# DSOBoard.net
KiCad netlist of a schematic drawn in Altium Designer
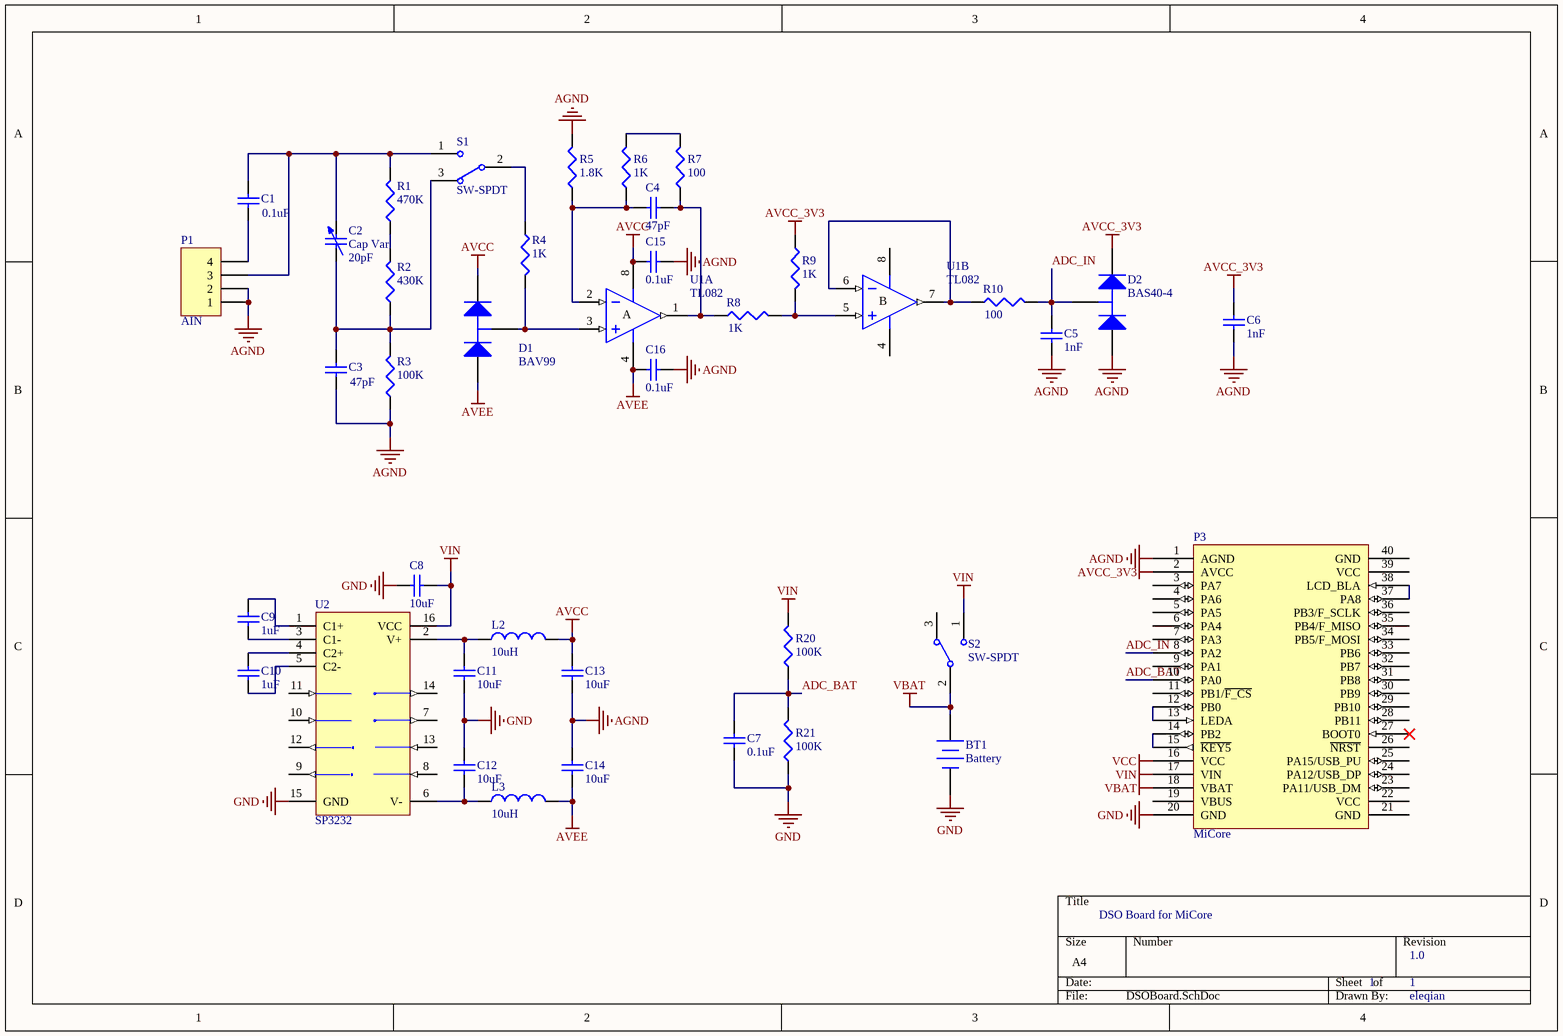
[diagram p0: DSOBoard.SchDoc]

(export (version "E")
  (design (tool "Eeschema 10.0.6"))
  (components
    (comp (ref "BT1")
      (value "Battery")
      (footprint "BAT-2")
      (description "Multicell Battery")
      (fields (field (name "PUBLISHER") "Altium Limited"))
      (libsource (lib "Miscellaneous Devices") (part "Battery"))
    )
    (comp (ref "C1")
      (value "0.1uF")
      (footprint "0805C")
      (description "Capacitor")
      (fields (field (name "Comment") "Cap") (field (name "PUBLISHER") "Altium Limited"))
      (libsource (lib "Miscellaneous Devices") (part "Cap"))
    )
    (comp (ref "C2")
      (value "Cap Var")
      (footprint "C1210_N")
      (description "Variable or Adjustable Capacitor")
      (fields (field (name "ALTIUM_VALUE") "20pF") (field (name "PUBLISHER") "Altium Limited"))
      (libsource (lib "Miscellaneous Devices") (part "Cap Var"))
    )
    (comp (ref "C3")
      (value "47pF")
      (footprint "0603C")
      (description "Capacitor")
      (fields (field (name "Comment") "Cap"))
      (libsource (lib "Miscellaneous Devices") (part "Cap"))
    )
    (comp (ref "C4")
      (value "47pF")
      (footprint "0603C")
      (description "Capacitor")
      (fields (field (name "Comment") "Cap"))
      (libsource (lib "Miscellaneous Devices") (part "Cap"))
    )
    (comp (ref "C5")
      (value "1nF")
      (footprint "0603C")
      (description "Capacitor")
      (fields (field (name "Comment") "Cap"))
      (libsource (lib "Miscellaneous Devices") (part "Cap"))
    )
    (comp (ref "C6")
      (value "1nF")
      (footprint "0603C")
      (description "Capacitor")
      (fields (field (name "Comment") "Cap"))
      (libsource (lib "Miscellaneous Devices") (part "Cap"))
    )
    (comp (ref "C7")
      (value "0.1uF")
      (footprint "0603C")
      (description "Capacitor")
      (fields (field (name "Comment") "Cap"))
      (libsource (lib "Miscellaneous Devices") (part "Cap"))
    )
    (comp (ref "C8")
      (value "10uF")
      (footprint "0603C")
      (description "Capacitor")
      (fields (field (name "Comment") "Cap") (field (name "PUBLISHER") "Altium Limited"))
      (libsource (lib "Miscellaneous Devices") (part "Cap"))
    )
    (comp (ref "C9")
      (value "1uF")
      (footprint "0603C")
      (description "Capacitor")
      (fields (field (name "Comment") "Cap") (field (name "PUBLISHER") "Altium Limited"))
      (libsource (lib "Miscellaneous Devices") (part "Cap"))
    )
    (comp (ref "C10")
      (value "1uF")
      (footprint "0603C")
      (description "Capacitor")
      (fields (field (name "Comment") "Cap") (field (name "PUBLISHER") "Altium Limited"))
      (libsource (lib "Miscellaneous Devices") (part "Cap"))
    )
    (comp (ref "C11")
      (value "10uF")
      (footprint "0603C")
      (description "Capacitor")
      (fields (field (name "Comment") "Cap") (field (name "PUBLISHER") "Altium Limited"))
      (libsource (lib "Miscellaneous Devices") (part "Cap"))
    )
    (comp (ref "C12")
      (value "10uF")
      (footprint "0603C")
      (description "Capacitor")
      (fields (field (name "Comment") "Cap") (field (name "PUBLISHER") "Altium Limited"))
      (libsource (lib "Miscellaneous Devices") (part "Cap"))
    )
    (comp (ref "C13")
      (value "10uF")
      (footprint "0603C")
      (description "Capacitor")
      (fields (field (name "Comment") "Cap"))
      (libsource (lib "Miscellaneous Devices") (part "Cap"))
    )
    (comp (ref "C14")
      (value "10uF")
      (footprint "0603C")
      (description "Capacitor")
      (fields (field (name "Comment") "Cap"))
      (libsource (lib "Miscellaneous Devices") (part "Cap"))
    )
    (comp (ref "C15")
      (value "0.1uF")
      (footprint "0603C")
      (description "Capacitor")
      (fields (field (name "Comment") "Cap"))
      (libsource (lib "Miscellaneous Devices") (part "Cap"))
    )
    (comp (ref "C16")
      (value "0.1uF")
      (footprint "0603C")
      (description "Capacitor")
      (fields (field (name "Comment") "Cap"))
      (libsource (lib "Miscellaneous Devices") (part "Cap"))
    )
    (comp (ref "D1")
      (value "BAV99")
      (footprint "SOT-23")
      (description "SOT23 Silicon Planar High-Speed Switching Series Diode Pair")
      (fields (field (name "PUBLISHER") "Altium Limited"))
      (libsource (lib "Zetex Discrete Diode") (part "BAV99"))
    )
    (comp (ref "D2")
      (value "BAS40-4")
      (footprint "SOT-23")
      (description "SOT23 Silicon Planar High-Speed Switching Series Diode Pair")
      (fields (field (name "PUBLISHER") "Altium Limited"))
      (libsource (lib "Zetex Discrete Diode") (part "BAV99"))
    )
    (comp (ref "L2")
      (value "10uH")
      (footprint "0805L")
      (description "Inductor")
      (fields (field (name "PUBLISHER") "Altium Limited"))
      (libsource (lib "Miscellaneous Devices") (part "Inductor"))
    )
    (comp (ref "L3")
      (value "10uH")
      (footprint "0805L")
      (description "Inductor")
      (fields (field (name "PUBLISHER") "Altium Limited"))
      (libsource (lib "Miscellaneous Devices") (part "Inductor"))
    )
    (comp (ref "P1")
      (value "AIN")
      (footprint "HDR1X4")
      (description "Header, 4-Pin")
      (fields (field (name "PUBLISHER") "Altium Limited"))
      (libsource (lib "Miscellaneous Connectors") (part "Header 4"))
    )
    (comp (ref "P3") (value "MiCore") (description "MiCore核心板") (libsource (lib "MiCore") (part "MiCore")))
    (comp (ref "R1")
      (value "470K")
      (footprint "0603R")
      (description "Resistor")
      (fields (field (name "Comment") "Res3") (field (name "PUBLISHER") "Altium Limited"))
      (libsource (lib "Miscellaneous Devices") (part "Res3"))
    )
    (comp (ref "R2")
      (value "430K")
      (footprint "0603R")
      (description "Resistor")
      (fields (field (name "Comment") "Res3") (field (name "PUBLISHER") "Altium Limited"))
      (libsource (lib "Miscellaneous Devices") (part "Res3"))
    )
    (comp (ref "R3")
      (value "100K")
      (footprint "0603R")
      (description "Resistor")
      (fields (field (name "Comment") "Res3") (field (name "PUBLISHER") "Altium Limited"))
      (libsource (lib "Miscellaneous Devices") (part "Res3"))
    )
    (comp (ref "R4")
      (value "1K")
      (footprint "0603R")
      (description "Resistor")
      (fields (field (name "Comment") "Res3") (field (name "PUBLISHER") "Altium Limited"))
      (libsource (lib "Miscellaneous Devices") (part "Res3"))
    )
    (comp (ref "R5")
      (value "1.8K")
      (footprint "0603R")
      (description "Resistor")
      (fields (field (name "Comment") "Res3") (field (name "PUBLISHER") "Altium Limited"))
      (libsource (lib "Miscellaneous Devices") (part "Res3"))
    )
    (comp (ref "R6")
      (value "1K")
      (footprint "0603R")
      (description "Resistor")
      (fields (field (name "Comment") "Res3") (field (name "PUBLISHER") "Altium Limited"))
      (libsource (lib "Miscellaneous Devices") (part "Res3"))
    )
    (comp (ref "R7")
      (value "100")
      (footprint "0603R")
      (description "Resistor")
      (fields (field (name "Comment") "Res3") (field (name "PUBLISHER") "Altium Limited"))
      (libsource (lib "Miscellaneous Devices") (part "Res3"))
    )
    (comp (ref "R8")
      (value "1K")
      (footprint "0603R")
      (description "Resistor")
      (fields (field (name "Comment") "Res3") (field (name "PUBLISHER") "Altium Limited"))
      (libsource (lib "Miscellaneous Devices") (part "Res3"))
    )
    (comp (ref "R9")
      (value "1K")
      (footprint "0603R")
      (description "Resistor")
      (fields (field (name "Comment") "Res3") (field (name "PUBLISHER") "Altium Limited"))
      (libsource (lib "Miscellaneous Devices") (part "Res3"))
    )
    (comp (ref "R10")
      (value "100")
      (footprint "0603R")
      (description "Resistor")
      (fields (field (name "Comment") "Res3") (field (name "PUBLISHER") "Altium Limited"))
      (libsource (lib "Miscellaneous Devices") (part "Res3"))
    )
    (comp (ref "R20")
      (value "100K")
      (footprint "0603R")
      (description "Resistor")
      (fields (field (name "Comment") "Res3") (field (name "PUBLISHER") "Altium Limited"))
      (libsource (lib "Miscellaneous Devices") (part "Res3"))
    )
    (comp (ref "R21")
      (value "100K")
      (footprint "0603R")
      (description "Resistor")
      (fields (field (name "Comment") "Res3") (field (name "PUBLISHER") "Altium Limited"))
      (libsource (lib "Miscellaneous Devices") (part "Res3"))
    )
    (comp (ref "S1")
      (value "SW-SPDT")
      (footprint "SPDT_3S")
      (description "SPDT Subminiature Toggle Switch, Right Angle Mounting, Vertical Actuation")
      (fields (field (name "PUBLISHER") "Altium Limited"))
      (libsource (lib "Miscellaneous Devices") (part "SW-SPDT"))
    )
    (comp (ref "S2")
      (value "SW-SPDT")
      (footprint "SPDT_3S")
      (description "SPDT Subminiature Toggle Switch, Right Angle Mounting, Vertical Actuation")
      (fields (field (name "PUBLISHER") "Altium Limited"))
      (libsource (lib "Miscellaneous Devices") (part "SW-SPDT"))
    )
    (comp (ref "U1")
      (value "TL082")
      (footprint "SO-8_N")
      (description "Dual, 16MHz, Rail-to-Rail FET-Input Amplifier")
      (fields (field (name "PUBLISHER") "Altium Limited"))
      (libsource (lib "AD Operational Amplifier") (part "AD823AR"))
    )
    (comp (ref "U2")
      (value "SP3232")
      (footprint "NSO16_N")
      (description "3.0V TO 5.5V, Low-Power, up to 1Mbps, True RS-232 Transceiver Using Four 0.1µF External Capacitor")
      (fields (field (name "PUBLISHER") "Altium Limited"))
      (libsource (lib "Maxim Communication Transceiver") (part "MAX3232CSE"))
    )
  )
  (nets
    (net (code "1") (name "/ADC_BAT") (class "Default")
      (node (ref "C7") (pin "2") (pinfunction "2_2") (pintype "passive"))
      (node (ref "P3") (pin "10") (pinfunction "PA0_10") (pintype "bidirectional"))
      (node (ref "R20") (pin "1") (pinfunction "1_1") (pintype "passive"))
      (node (ref "R21") (pin "2") (pinfunction "2_2") (pintype "passive"))
    )
    (net (code "2") (name "/ADC_IN") (class "Default")
      (node (ref "C5") (pin "2") (pinfunction "2_2") (pintype "passive"))
      (node (ref "D2") (pin "1") (pinfunction "C_1") (pintype "passive"))
      (node (ref "P3") (pin "8") (pinfunction "PA2_8") (pintype "bidirectional"))
      (node (ref "R10") (pin "2") (pinfunction "2_2") (pintype "passive"))
    )
    (net (code "3") (name "AGND") (class "Default")
      (node (ref "C13") (pin "2") (pinfunction "2_2") (pintype "passive"))
      (node (ref "C14") (pin "1") (pinfunction "1_1") (pintype "passive"))
      (node (ref "C15") (pin "1") (pinfunction "1_1") (pintype "passive"))
      (node (ref "C16") (pin "1") (pinfunction "1_1") (pintype "passive"))
      (node (ref "C3") (pin "1") (pinfunction "1_1") (pintype "passive"))
      (node (ref "C5") (pin "1") (pinfunction "1_1") (pintype "passive"))
      (node (ref "C6") (pin "1") (pinfunction "1_1") (pintype "passive"))
      (node (ref "D2") (pin "3") (pinfunction "A_3") (pintype "passive"))
      (node (ref "P1") (pin "1") (pinfunction "1_1") (pintype "passive"))
      (node (ref "P1") (pin "2") (pinfunction "2_2") (pintype "passive"))
      (node (ref "P3") (pin "1") (pinfunction "AGND_1") (pintype "power_in"))
      (node (ref "R3") (pin "1") (pinfunction "1_1") (pintype "passive"))
      (node (ref "R5") (pin "2") (pinfunction "2_2") (pintype "passive"))
    )
    (net (code "4") (name "AVCC") (class "Default")
      (node (ref "C13") (pin "1") (pinfunction "1_1") (pintype "passive"))
      (node (ref "C15") (pin "2") (pinfunction "2_2") (pintype "passive"))
      (node (ref "D1") (pin "2") (pinfunction "K_2") (pintype "passive"))
      (node (ref "L2") (pin "2") (pinfunction "2_2") (pintype "passive"))
      (node (ref "U1") (pin "8") (pinfunction "V+_8") (pintype "power_in"))
    )
    (net (code "5") (name "AVCC_3V3") (class "Default")
      (node (ref "C6") (pin "2") (pinfunction "2_2") (pintype "passive"))
      (node (ref "D2") (pin "2") (pinfunction "K_2") (pintype "passive"))
      (node (ref "P3") (pin "2") (pinfunction "AVCC_2") (pintype "power_in"))
      (node (ref "R9") (pin "1") (pinfunction "1_1") (pintype "passive"))
    )
    (net (code "6") (name "AVEE") (class "Default")
      (node (ref "C14") (pin "2") (pinfunction "2_2") (pintype "passive"))
      (node (ref "C16") (pin "2") (pinfunction "2_2") (pintype "passive"))
      (node (ref "D1") (pin "3") (pinfunction "A_3") (pintype "passive"))
      (node (ref "L3") (pin "2") (pinfunction "2_2") (pintype "passive"))
      (node (ref "U1") (pin "4") (pinfunction "V-_4") (pintype "power_in"))
    )
    (net (code "7") (name "GND") (class "Default")
      (node (ref "BT1") (pin "2") (pinfunction "-_2") (pintype "passive"))
      (node (ref "C11") (pin "2") (pinfunction "2_2") (pintype "passive"))
      (node (ref "C12") (pin "2") (pinfunction "2_2") (pintype "passive"))
      (node (ref "C7") (pin "1") (pinfunction "1_1") (pintype "passive"))
      (node (ref "C8") (pin "2") (pinfunction "2_2") (pintype "passive"))
      (node (ref "P3") (pin "20") (pinfunction "GND_20") (pintype "power_in"))
      (node (ref "R21") (pin "1") (pinfunction "1_1") (pintype "passive"))
      (node (ref "U2") (pin "15") (pinfunction "GND_15") (pintype "power_in"))
    )
    (net (code "8") (name "Net-(C1-Pad1)") (class "Default")
      (node (ref "C1") (pin "1") (pinfunction "1_1") (pintype "passive"))
      (node (ref "C2") (pin "2") (pinfunction "2_2") (pintype "passive"))
      (node (ref "P1") (pin "3") (pinfunction "3_3") (pintype "passive"))
      (node (ref "R1") (pin "2") (pinfunction "2_2") (pintype "passive"))
      (node (ref "S1") (pin "1") (pinfunction "1_1") (pintype "passive"))
    )
    (net (code "9") (name "Net-(C1-Pad2)") (class "Default")
      (node (ref "C1") (pin "2") (pinfunction "2_2") (pintype "passive"))
      (node (ref "P1") (pin "4") (pinfunction "4_4") (pintype "passive"))
    )
    (net (code "10") (name "Net-(C2-Pad1)") (class "Default")
      (node (ref "C2") (pin "1") (pinfunction "1_1") (pintype "passive"))
      (node (ref "C3") (pin "2") (pinfunction "2_2") (pintype "passive"))
      (node (ref "R2") (pin "1") (pinfunction "1_1") (pintype "passive"))
      (node (ref "R3") (pin "2") (pinfunction "2_2") (pintype "passive"))
      (node (ref "S1") (pin "3") (pinfunction "3_3") (pintype "passive"))
    )
    (net (code "11") (name "Net-(D1-C)") (class "Default")
      (node (ref "D1") (pin "1") (pinfunction "C_1") (pintype "passive"))
      (node (ref "R4") (pin "2") (pinfunction "2_2") (pintype "passive"))
      (node (ref "U1") (pin "3") (pinfunction "IN+_3") (pintype "input"))
    )
    (net (code "12") (name "Net-(P3-LCD_BLA)") (class "Default")
      (node (ref "P3") (pin "37") (pinfunction "PA8_37") (pintype "bidirectional"))
      (node (ref "P3") (pin "38") (pinfunction "LCD_BLA_38") (pintype "input"))
    )
    (net (code "13") (name "Net-(P3-LEDA)") (class "Default")
      (node (ref "P3") (pin "12") (pinfunction "PB0_12") (pintype "bidirectional"))
      (node (ref "P3") (pin "13") (pinfunction "LEDA_13") (pintype "input"))
    )
    (net (code "14") (name "Net-(P3-PB2)") (class "Default")
      (node (ref "P3") (pin "14") (pinfunction "PB2_14") (pintype "bidirectional"))
      (node (ref "P3") (pin "15") (pinfunction "~{KEY5}_15") (pintype "output"))
    )
    (net (code "15") (name "Net-(R1-Pad1)") (class "Default")
      (node (ref "R1") (pin "1") (pinfunction "1_1") (pintype "passive"))
      (node (ref "R2") (pin "2") (pinfunction "2_2") (pintype "passive"))
    )
    (net (code "16") (name "Net-(R4-Pad1)") (class "Default")
      (node (ref "R4") (pin "1") (pinfunction "1_1") (pintype "passive"))
      (node (ref "S1") (pin "2") (pinfunction "2_2") (pintype "passive"))
    )
    (net (code "17") (name "Net-(R6-Pad2)") (class "Default")
      (node (ref "R6") (pin "2") (pinfunction "2_2") (pintype "passive"))
      (node (ref "R7") (pin "2") (pinfunction "2_2") (pintype "passive"))
    )
    (net (code "18") (name "Net-(U1A-IN-)") (class "Default")
      (node (ref "C4") (pin "2") (pinfunction "2_2") (pintype "passive"))
      (node (ref "R5") (pin "1") (pinfunction "1_1") (pintype "passive"))
      (node (ref "R6") (pin "1") (pinfunction "1_1") (pintype "passive"))
      (node (ref "U1") (pin "2") (pinfunction "IN-_2") (pintype "input"))
    )
    (net (code "19") (name "Net-(U1A-OUT)") (class "Default")
      (node (ref "C4") (pin "1") (pinfunction "1_1") (pintype "passive"))
      (node (ref "R7") (pin "1") (pinfunction "1_1") (pintype "passive"))
      (node (ref "R8") (pin "1") (pinfunction "1_1") (pintype "passive"))
      (node (ref "U1") (pin "1") (pinfunction "OUT_1") (pintype "output"))
    )
    (net (code "20") (name "Net-(U1B-IN+)") (class "Default")
      (node (ref "R8") (pin "2") (pinfunction "2_2") (pintype "passive"))
      (node (ref "R9") (pin "2") (pinfunction "2_2") (pintype "passive"))
      (node (ref "U1") (pin "5") (pinfunction "IN+_5") (pintype "input"))
    )
    (net (code "21") (name "Net-(U1B-IN-)") (class "Default")
      (node (ref "R10") (pin "1") (pinfunction "1_1") (pintype "passive"))
      (node (ref "U1") (pin "6") (pinfunction "IN-_6") (pintype "input"))
      (node (ref "U1") (pin "7") (pinfunction "OUT_7") (pintype "output"))
    )
    (net (code "22") (name "Net-(U2-C1+)") (class "Default")
      (node (ref "C9") (pin "1") (pinfunction "1_1") (pintype "passive"))
      (node (ref "U2") (pin "1") (pinfunction "C1+_1") (pintype "passive"))
    )
    (net (code "23") (name "Net-(U2-C1-)") (class "Default")
      (node (ref "C9") (pin "2") (pinfunction "2_2") (pintype "passive"))
      (node (ref "U2") (pin "3") (pinfunction "C1-_3") (pintype "passive"))
    )
    (net (code "24") (name "Net-(U2-C2+)") (class "Default")
      (node (ref "C10") (pin "1") (pinfunction "1_1") (pintype "passive"))
      (node (ref "U2") (pin "4") (pinfunction "C2+_4") (pintype "passive"))
    )
    (net (code "25") (name "Net-(U2-C2-)") (class "Default")
      (node (ref "C10") (pin "2") (pinfunction "2_2") (pintype "passive"))
      (node (ref "U2") (pin "5") (pinfunction "C2-_5") (pintype "passive"))
    )
    (net (code "26") (name "Net-(U2-V+)") (class "Default")
      (node (ref "C11") (pin "1") (pinfunction "1_1") (pintype "passive"))
      (node (ref "L2") (pin "1") (pinfunction "1_1") (pintype "passive"))
      (node (ref "U2") (pin "2") (pinfunction "V+_2") (pintype "power_in"))
    )
    (net (code "27") (name "Net-(U2-V-)") (class "Default")
      (node (ref "C12") (pin "1") (pinfunction "1_1") (pintype "passive"))
      (node (ref "L3") (pin "1") (pinfunction "1_1") (pintype "passive"))
      (node (ref "U2") (pin "6") (pinfunction "V-_6") (pintype "power_in"))
    )
    (net (code "28") (name "VBAT") (class "Default")
      (node (ref "BT1") (pin "1") (pinfunction "+_1") (pintype "passive"))
      (node (ref "P3") (pin "18") (pinfunction "VBAT_18") (pintype "power_in"))
      (node (ref "S2") (pin "2") (pinfunction "2_2") (pintype "passive"))
    )
    (net (code "29") (name "VCC") (class "Default")
      (node (ref "P3") (pin "16") (pinfunction "VCC_16") (pintype "power_in"))
    )
    (net (code "30") (name "VIN") (class "Default")
      (node (ref "C8") (pin "1") (pinfunction "1_1") (pintype "passive"))
      (node (ref "P3") (pin "17") (pinfunction "VIN_17") (pintype "power_in"))
      (node (ref "R20") (pin "2") (pinfunction "2_2") (pintype "passive"))
      (node (ref "S2") (pin "1") (pinfunction "1_1") (pintype "passive"))
      (node (ref "U2") (pin "16") (pinfunction "VCC_16") (pintype "power_in"))
    )
    (net (code "31") (name "unconnected-(P3-BOOT0-Pad27)") (class "Default")
      (node (ref "P3") (pin "27") (pinfunction "BOOT0_27") (pintype "input+no_connect"))
    )
    (net (code "32") (name "unconnected-(P3-GND-Pad21)") (class "Default")
      (node (ref "P3") (pin "21") (pinfunction "GND_21") (pintype "power_in"))
    )
    (net (code "33") (name "unconnected-(P3-GND-Pad40)") (class "Default")
      (node (ref "P3") (pin "40") (pinfunction "GND_40") (pintype "power_in"))
    )
    (net (code "34") (name "unconnected-(P3-PA1-Pad9)") (class "Default")
      (node (ref "P3") (pin "9") (pinfunction "PA1_9") (pintype "bidirectional"))
    )
    (net (code "35") (name "unconnected-(P3-PA3-Pad7)") (class "Default")
      (node (ref "P3") (pin "7") (pinfunction "PA3_7") (pintype "bidirectional"))
    )
    (net (code "36") (name "unconnected-(P3-PA4-Pad6)") (class "Default")
      (node (ref "P3") (pin "6") (pinfunction "PA4_6") (pintype "bidirectional"))
    )
    (net (code "37") (name "unconnected-(P3-PA5-Pad5)") (class "Default")
      (node (ref "P3") (pin "5") (pinfunction "PA5_5") (pintype "bidirectional"))
    )
    (net (code "38") (name "unconnected-(P3-PA6-Pad4)") (class "Default")
      (node (ref "P3") (pin "4") (pinfunction "PA6_4") (pintype "bidirectional"))
    )
    (net (code "39") (name "unconnected-(P3-PA7-Pad3)") (class "Default")
      (node (ref "P3") (pin "3") (pinfunction "PA7_3") (pintype "bidirectional"))
    )
    (net (code "40") (name "unconnected-(P3-PA11{slash}USB_DM-Pad23)") (class "Default")
      (node (ref "P3") (pin "23") (pinfunction "PA11/USB_DM_23") (pintype "bidirectional"))
    )
    (net (code "41") (name "unconnected-(P3-PA12{slash}USB_DP-Pad24)") (class "Default")
      (node (ref "P3") (pin "24") (pinfunction "PA12/USB_DP_24") (pintype "bidirectional"))
    )
    (net (code "42") (name "unconnected-(P3-PA15{slash}USB_PU-Pad25)") (class "Default")
      (node (ref "P3") (pin "25") (pinfunction "PA15/USB_PU_25") (pintype "bidirectional"))
    )
    (net (code "43") (name "unconnected-(P3-PB1{slash}~{F_CS}-Pad11)") (class "Default")
      (node (ref "P3") (pin "11") (pinfunction "PB1/~{F_CS}_11") (pintype "bidirectional"))
    )
    (net (code "44") (name "unconnected-(P3-PB3{slash}F_SCLK-Pad36)") (class "Default")
      (node (ref "P3") (pin "36") (pinfunction "PB3/F_SCLK_36") (pintype "bidirectional"))
    )
    (net (code "45") (name "unconnected-(P3-PB4{slash}F_MISO-Pad35)") (class "Default")
      (node (ref "P3") (pin "35") (pinfunction "PB4/F_MISO_35") (pintype "bidirectional"))
    )
    (net (code "46") (name "unconnected-(P3-PB5{slash}F_MOSI-Pad34)") (class "Default")
      (node (ref "P3") (pin "34") (pinfunction "PB5/F_MOSI_34") (pintype "bidirectional"))
    )
    (net (code "47") (name "unconnected-(P3-PB6-Pad33)") (class "Default")
      (node (ref "P3") (pin "33") (pinfunction "PB6_33") (pintype "bidirectional"))
    )
    (net (code "48") (name "unconnected-(P3-PB7-Pad32)") (class "Default")
      (node (ref "P3") (pin "32") (pinfunction "PB7_32") (pintype "bidirectional"))
    )
    (net (code "49") (name "unconnected-(P3-PB8-Pad31)") (class "Default")
      (node (ref "P3") (pin "31") (pinfunction "PB8_31") (pintype "bidirectional"))
    )
    (net (code "50") (name "unconnected-(P3-PB9-Pad30)") (class "Default")
      (node (ref "P3") (pin "30") (pinfunction "PB9_30") (pintype "bidirectional"))
    )
    (net (code "51") (name "unconnected-(P3-PB10-Pad29)") (class "Default")
      (node (ref "P3") (pin "29") (pinfunction "PB10_29") (pintype "bidirectional"))
    )
    (net (code "52") (name "unconnected-(P3-PB11-Pad28)") (class "Default")
      (node (ref "P3") (pin "28") (pinfunction "PB11_28") (pintype "bidirectional"))
    )
    (net (code "53") (name "unconnected-(P3-VBUS-Pad19)") (class "Default")
      (node (ref "P3") (pin "19") (pinfunction "VBUS_19") (pintype "power_in"))
    )
    (net (code "54") (name "unconnected-(P3-VCC-Pad22)") (class "Default")
      (node (ref "P3") (pin "22") (pinfunction "VCC_22") (pintype "power_in"))
    )
    (net (code "55") (name "unconnected-(P3-VCC-Pad39)") (class "Default")
      (node (ref "P3") (pin "39") (pinfunction "VCC_39") (pintype "power_in"))
    )
    (net (code "56") (name "unconnected-(P3-~{NRST}-Pad26)") (class "Default")
      (node (ref "P3") (pin "26") (pinfunction "~{NRST}_26") (pintype "open_collector"))
    )
    (net (code "57") (name "unconnected-(S2-Pad3)") (class "Default")
      (node (ref "S2") (pin "3") (pinfunction "3_3") (pintype "passive"))
    )
    (net (code "58") (name "unconnected-(U1B-V+-Pad8)") (class "Default")
      (node (ref "U1") (pin "8") (pinfunction "V+_8") (pintype "power_in"))
    )
    (net (code "59") (name "unconnected-(U1B-V--Pad4)") (class "Default")
      (node (ref "U1") (pin "4") (pinfunction "V-_4") (pintype "power_in"))
    )
    (net (code "60") (name "unconnected-(U2-R1IN-Pad13)") (class "Default")
      (node (ref "U2") (pin "13") (pinfunction "R1IN_13") (pintype "input"))
    )
    (net (code "61") (name "unconnected-(U2-R1OUT-Pad12)") (class "Default")
      (node (ref "U2") (pin "12") (pinfunction "R1OUT_12") (pintype "output"))
    )
    (net (code "62") (name "unconnected-(U2-R2IN-Pad8)") (class "Default")
      (node (ref "U2") (pin "8") (pinfunction "R2IN_8") (pintype "input"))
    )
    (net (code "63") (name "unconnected-(U2-R2OUT-Pad9)") (class "Default")
      (node (ref "U2") (pin "9") (pinfunction "R2OUT_9") (pintype "output"))
    )
    (net (code "64") (name "unconnected-(U2-T1IN-Pad11)") (class "Default")
      (node (ref "U2") (pin "11") (pinfunction "T1IN_11") (pintype "input"))
    )
    (net (code "65") (name "unconnected-(U2-T1OUT-Pad14)") (class "Default")
      (node (ref "U2") (pin "14") (pinfunction "T1OUT_14") (pintype "output"))
    )
    (net (code "66") (name "unconnected-(U2-T2IN-Pad10)") (class "Default")
      (node (ref "U2") (pin "10") (pinfunction "T2IN_10") (pintype "input"))
    )
    (net (code "67") (name "unconnected-(U2-T2OUT-Pad7)") (class "Default")
      (node (ref "U2") (pin "7") (pinfunction "T2OUT_7") (pintype "output"))
    )
  )
)
